# Driver.net
KiCad netlist of a schematic drawn in Altium Designer
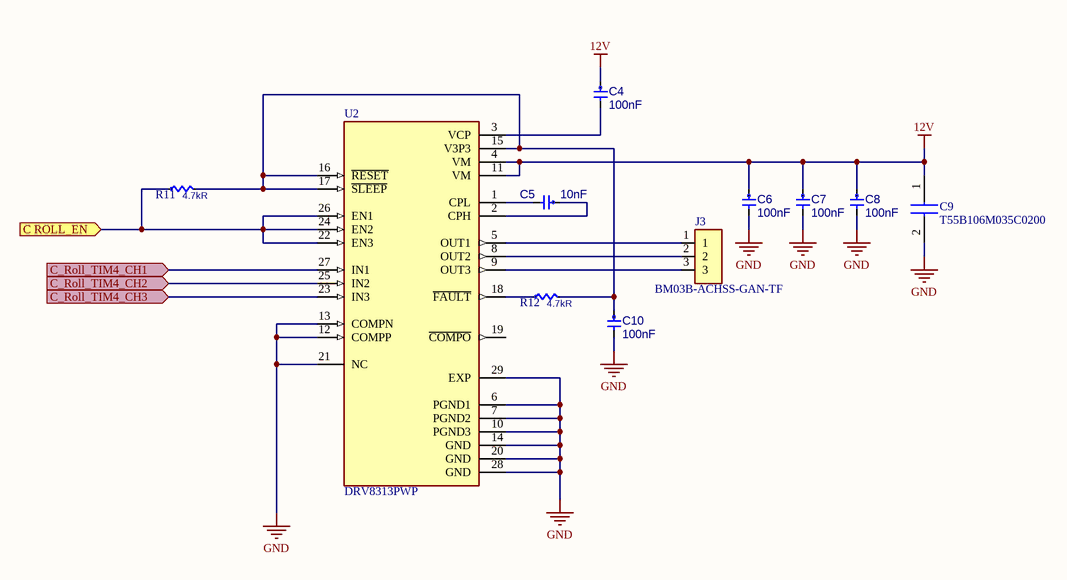
[diagram p0: Driver.SchDoc]

(export (version "E")
  (design (tool "Eeschema 10.0.6"))
  (components
    (comp (ref "C4")
      (value "C0603C104M5RACTU")
      (footprint "CAP0603")
      (description "CAP CER 0.1UF 50V X7R 0603")
      (fields (field (name "TOLERANCE") "20%") (field (name "CAPACITANCE") "100nF"))
      (libsource (lib "rtr") (part "CMP-00691-1"))
    )
    (comp (ref "C5")
      (value "C0603C103M5RACTU")
      (footprint "CAP0603")
      (description "CAP CER 10NF 50V X7R 0603")
      (fields (field (name "TOLERANCE") "20%") (field (name "CAPACITANCE") "10nF"))
      (libsource (lib "rtr") (part "CMP-00691-1"))
    )
    (comp (ref "C6")
      (value "C0603C104M5RACTU")
      (footprint "CAP0603")
      (description "CAP CER 0.1UF 50V X7R 0603")
      (fields (field (name "TOLERANCE") "20%") (field (name "CAPACITANCE") "100nF"))
      (libsource (lib "rtr") (part "CMP-00691-1"))
    )
    (comp (ref "C7")
      (value "C0603C104M5RACTU")
      (footprint "CAP0603")
      (description "CAP CER 0.1UF 50V X7R 0603")
      (fields (field (name "TOLERANCE") "20%") (field (name "CAPACITANCE") "100nF"))
      (libsource (lib "rtr") (part "CMP-00691-1"))
    )
    (comp (ref "C8")
      (value "C0603C104M5RACTU")
      (footprint "CAP0603")
      (description "CAP CER 0.1UF 50V X7R 0603")
      (fields (field (name "TOLERANCE") "20%") (field (name "CAPACITANCE") "100nF"))
      (libsource (lib "rtr") (part "CMP-00691-1"))
    )
    (comp (ref "C9")
      (value "T55B106M035C0200")
      (footprint "T55B106M035C0200")
      (description "Capacitor")
      (fields (field (name "MOUSER PART NUMBER") "74-T55B106M035C0200"))
      (libsource (lib "T55B106M035C0200") (part "T55B106M035C0200"))
    )
    (comp (ref "C10")
      (value "C0603C104M5RACTU")
      (footprint "CAP0603")
      (description "CAP CER 0.1UF 50V X7R 0603")
      (fields (field (name "TOLERANCE") "20%") (field (name "CAPACITANCE") "100nF"))
      (libsource (lib "rtr") (part "CMP-00691-1"))
    )
    (comp (ref "J3")
      (value "BM03B-ACHSS-GAN-TF")
      (footprint "BM03B-ACHSS-GAN-TF")
      (description "ACH Series 3 Position 1.2 mm Pitch Disconnectable Crimp Style Housing")
      (libsource (lib "SM02B-SFKH-TF") (part "BM03B-ACHSS-GAN-TF"))
    )
    (comp (ref "R11")
      (value "RC0603JR-074K7L")
      (footprint "RES0603")
      (description "RES SMD 4.7K OHM 5% 1/10W 0603")
      (fields (field (name "TOLERANCE") "5%") (field (name "RESISTANCE") "4.7kR"))
      (libsource (lib "rtr") (part "CMP-01404-1"))
    )
    (comp (ref "R12")
      (value "RC0603JR-074K7L")
      (footprint "RES0603")
      (description "RES SMD 4.7K OHM 5% 1/10W 0603")
      (fields (field (name "TOLERANCE") "5%") (field (name "RESISTANCE") "4.7kR"))
      (libsource (lib "rtr") (part "CMP-01404-1"))
    )
    (comp (ref "U2")
      (value "DRV8313PWP")
      (footprint "DRV8313PWP")
      (description "65-V max, 3-A peak 3-phase motor driver")
      (fields (field (name "MF") "Texas Instruments"))
      (libsource (lib "RTR") (part "DRV8313PWP"))
    )
  )
  (nets
    (net (code "1") (name "/C ROLL_EN") (class "Default")
      (node (ref "R11") (pin "1") (pinfunction "1_1") (pintype "passive"))
      (node (ref "U2") (pin "22") (pinfunction "EN3_22") (pintype "input"))
      (node (ref "U2") (pin "24") (pinfunction "EN2_24") (pintype "input"))
      (node (ref "U2") (pin "26") (pinfunction "EN1_26") (pintype "input"))
    )
    (net (code "2") (name "/C_Roll_TIM4_CH1") (class "Default")
      (node (ref "U2") (pin "27") (pinfunction "IN1_27") (pintype "input"))
    )
    (net (code "3") (name "/C_Roll_TIM4_CH2") (class "Default")
      (node (ref "U2") (pin "25") (pinfunction "IN2_25") (pintype "input"))
    )
    (net (code "4") (name "/C_Roll_TIM4_CH3") (class "Default")
      (node (ref "U2") (pin "23") (pinfunction "IN3_23") (pintype "input"))
    )
    (net (code "5") (name "12V") (class "Default")
      (node (ref "C4") (pin "1") (pinfunction "1_1") (pintype "passive"))
      (node (ref "C6") (pin "1") (pinfunction "1_1") (pintype "passive"))
      (node (ref "C7") (pin "1") (pinfunction "1_1") (pintype "passive"))
      (node (ref "C8") (pin "1") (pinfunction "1_1") (pintype "passive"))
      (node (ref "C9") (pin "1") (pinfunction "1_1") (pintype "passive"))
      (node (ref "U2") (pin "11") (pinfunction "VM_11") (pintype "power_in"))
      (node (ref "U2") (pin "4") (pinfunction "VM_4") (pintype "power_in"))
    )
    (net (code "6") (name "GND") (class "Default")
      (node (ref "C10") (pin "2") (pinfunction "2_2") (pintype "passive"))
      (node (ref "C6") (pin "2") (pinfunction "2_2") (pintype "passive"))
      (node (ref "C7") (pin "2") (pinfunction "2_2") (pintype "passive"))
      (node (ref "C8") (pin "2") (pinfunction "2_2") (pintype "passive"))
      (node (ref "C9") (pin "2") (pinfunction "2_2") (pintype "passive"))
      (node (ref "U2") (pin "10") (pinfunction "PGND3_10") (pintype "power_in"))
      (node (ref "U2") (pin "12") (pinfunction "COMPP_12") (pintype "input"))
      (node (ref "U2") (pin "13") (pinfunction "COMPN_13") (pintype "input"))
      (node (ref "U2") (pin "14") (pinfunction "GND_14") (pintype "power_in"))
      (node (ref "U2") (pin "20") (pinfunction "GND_20") (pintype "power_in"))
      (node (ref "U2") (pin "21") (pinfunction "NC_21") (pintype "passive"))
      (node (ref "U2") (pin "28") (pinfunction "GND_28") (pintype "power_in"))
      (node (ref "U2") (pin "29") (pinfunction "EXP_29") (pintype "power_in"))
      (node (ref "U2") (pin "6") (pinfunction "PGND1_6") (pintype "power_in"))
      (node (ref "U2") (pin "7") (pinfunction "PGND2_7") (pintype "power_in"))
    )
    (net (code "7") (name "Net-(U2-CPH)") (class "Default")
      (node (ref "C5") (pin "1") (pinfunction "1_1") (pintype "passive"))
      (node (ref "U2") (pin "2") (pinfunction "CPH_2") (pintype "power_in"))
    )
    (net (code "8") (name "Net-(U2-CPL)") (class "Default")
      (node (ref "C5") (pin "2") (pinfunction "2_2") (pintype "passive"))
      (node (ref "U2") (pin "1") (pinfunction "CPL_1") (pintype "power_in"))
    )
    (net (code "9") (name "Net-(U2-OUT1)") (class "Default")
      (node (ref "J3") (pin "1") (pinfunction "1_1") (pintype "passive"))
      (node (ref "U2") (pin "5") (pinfunction "OUT1_5") (pintype "output"))
    )
    (net (code "10") (name "Net-(U2-OUT2)") (class "Default")
      (node (ref "J3") (pin "2") (pinfunction "2_2") (pintype "passive"))
      (node (ref "U2") (pin "8") (pinfunction "OUT2_8") (pintype "output"))
    )
    (net (code "11") (name "Net-(U2-OUT3)") (class "Default")
      (node (ref "J3") (pin "3") (pinfunction "3_3") (pintype "passive"))
      (node (ref "U2") (pin "9") (pinfunction "OUT3_9") (pintype "output"))
    )
    (net (code "12") (name "Net-(U2-V3P3)") (class "Default")
      (node (ref "C10") (pin "1") (pinfunction "1_1") (pintype "passive"))
      (node (ref "R11") (pin "2") (pinfunction "2_2") (pintype "passive"))
      (node (ref "R12") (pin "2") (pinfunction "2_2") (pintype "passive"))
      (node (ref "U2") (pin "15") (pinfunction "V3P3_15") (pintype "power_in"))
      (node (ref "U2") (pin "16") (pinfunction "~{RESET}_16") (pintype "input"))
      (node (ref "U2") (pin "17") (pinfunction "~{SLEEP}_17") (pintype "input"))
    )
    (net (code "13") (name "Net-(U2-VCP)") (class "Default")
      (node (ref "C4") (pin "2") (pinfunction "2_2") (pintype "passive"))
      (node (ref "U2") (pin "3") (pinfunction "VCP_3") (pintype "power_in"))
    )
    (net (code "14") (name "Net-(U2-~{FAULT})") (class "Default")
      (node (ref "R12") (pin "1") (pinfunction "1_1") (pintype "passive"))
      (node (ref "U2") (pin "18") (pinfunction "~{FAULT}_18") (pintype "output"))
    )
    (net (code "15") (name "unconnected-(U2-~{COMPO}-Pad19)") (class "Default")
      (node (ref "U2") (pin "19") (pinfunction "~{COMPO}_19") (pintype "output"))
    )
  )
)
